# Poseidon_SystemModule.net
KiCad netlist of a schematic drawn in Altium Designer
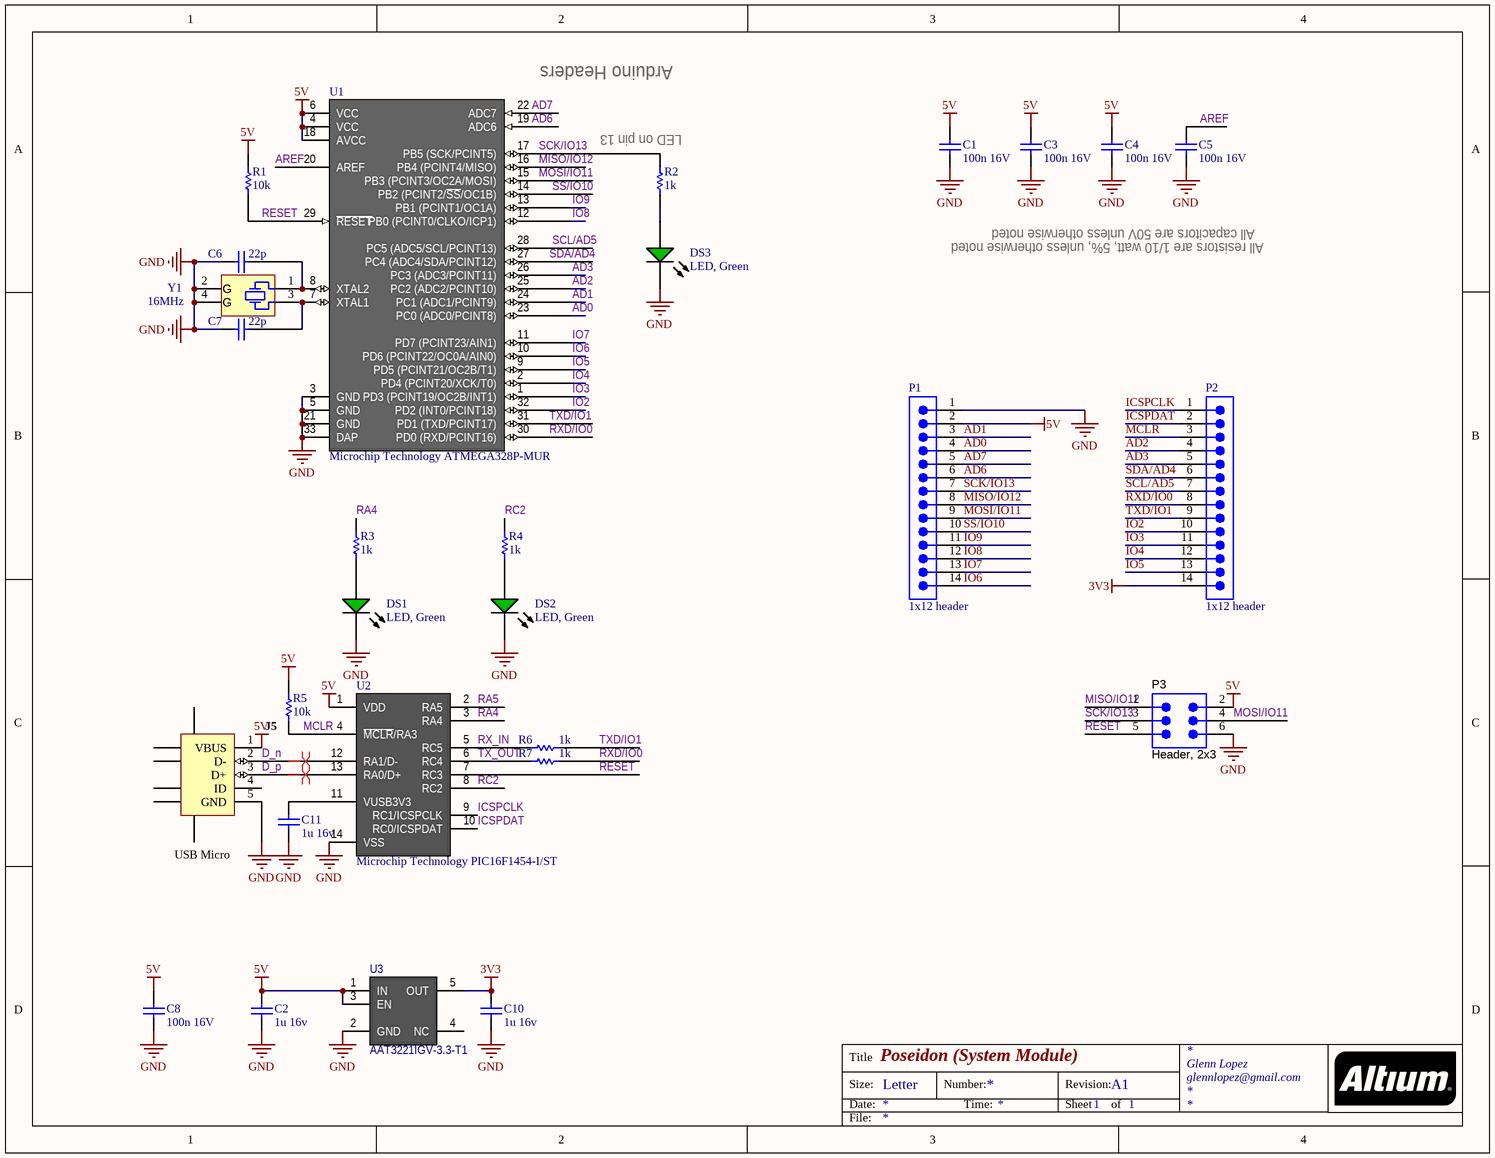
[diagram p0: Poseidon_SystemModule.SchDoc]

(export (version "E")
  (design (tool "Eeschema 10.0.6"))
  (components
    (comp (ref "C1")
      (value "100n 16V")
      (footprint "CAPC1005X55X30NL05T10")
      (description "Multilayer Ceramic Capacitors MLCC - SMD/SMT 16volts 0.1uF X7R 5%")
      (fields (field (name "MANUFACTURER PART NUMBER") "C0402C104J4RACTU") (field (name "TOLERANCE") "5 %"))
      (libsource (lib "CommunityVault") (part "CAP-2"))
    )
    (comp (ref "C2")
      (value "1u 16v")
      (footprint "CAPC1608X90X35ML15T15")
      (description "CAP CER 1UF 16V 10% X5R 0603")
      (fields (field (name "MANUFACTURER PART NUMBER") "0603YD105KAT2A"))
      (libsource (lib "CommunityVault") (part "CAP-2"))
    )
    (comp (ref "C3")
      (value "100n 16V")
      (footprint "CAPC1005X55X30NL05T10")
      (description "Multilayer Ceramic Capacitors MLCC - SMD/SMT 16volts 0.1uF X7R 5%")
      (fields (field (name "MANUFACTURER PART NUMBER") "C0402C104J4RACTU") (field (name "TOLERANCE") "5 %"))
      (libsource (lib "CommunityVault") (part "CAP-2"))
    )
    (comp (ref "C4")
      (value "100n 16V")
      (footprint "CAPC1005X55X30NL05T10")
      (description "Multilayer Ceramic Capacitors MLCC - SMD/SMT 16volts 0.1uF X7R 5%")
      (fields (field (name "MANUFACTURER PART NUMBER") "C0402C104J4RACTU") (field (name "TOLERANCE") "5 %"))
      (libsource (lib "CommunityVault") (part "CAP-2"))
    )
    (comp (ref "C5")
      (value "100n 16V")
      (footprint "CAPC1005X55X30NL05T10")
      (description "Multilayer Ceramic Capacitors MLCC - SMD/SMT 16volts 0.1uF X7R 5%")
      (fields (field (name "MANUFACTURER PART NUMBER") "C0402C104J4RACTU") (field (name "TOLERANCE") "5 %"))
      (libsource (lib "CommunityVault") (part "CAP-2"))
    )
    (comp (ref "C6")
      (value "22p")
      (footprint "CAPC1005X55X25LL05T05")
      (description "CAP CER 22PF 50V 5% NPO 0402")
      (fields (field (name "TOLERANCE") "±5%") (field (name "MANUFACTURER PART NUMBER") "CC0402JRNPO9BN220"))
      (libsource (lib "CommunityVault") (part "CAP-NP-2"))
    )
    (comp (ref "C7")
      (value "22p")
      (footprint "CAPC1005X55X25LL05T05")
      (description "CAP CER 22PF 50V 5% NPO 0402")
      (fields (field (name "TOLERANCE") "±5%") (field (name "MANUFACTURER PART NUMBER") "CC0402JRNPO9BN220"))
      (libsource (lib "CommunityVault") (part "CAP-NP-2"))
    )
    (comp (ref "C8")
      (value "100n 16V")
      (footprint "CAPC1005X55X30NL05T10")
      (description "Multilayer Ceramic Capacitors MLCC - SMD/SMT 16volts 0.1uF X7R 5%")
      (fields (field (name "MANUFACTURER PART NUMBER") "C0402C104J4RACTU") (field (name "TOLERANCE") "5 %"))
      (libsource (lib "CommunityVault") (part "CAP-2"))
    )
    (comp (ref "C10")
      (value "1u 16v")
      (footprint "CAPC1608X90X35ML15T15")
      (description "CAP CER 1UF 16V 10% X5R 0603")
      (fields (field (name "MANUFACTURER PART NUMBER") "0603YD105KAT2A"))
      (libsource (lib "CommunityVault") (part "CAP-2"))
    )
    (comp (ref "C11")
      (value "1u 16v")
      (footprint "CAPC1608X90X35ML15T15")
      (description "CAP CER 1UF 16V 10% X5R 0603")
      (fields (field (name "MANUFACTURER PART NUMBER") "0603YD105KAT2A"))
      (libsource (lib "CommunityVault") (part "CAP-2"))
    )
    (comp (ref "DS1")
      (value "LED, Green")
      (footprint "LTON_LTST-C190GKT")
      (description "LED GREEN CLEAR 0603 SMD")
      (fields (field (name "MANUFACTURER PART NUMBER") "LTST-C190GKT"))
      (libsource (lib "CommunityVault") (part "LED_GREEN_A1K2-2"))
    )
    (comp (ref "DS2")
      (value "LED, Green")
      (footprint "LTON_LTST-C190GKT")
      (description "LED GREEN CLEAR 0603 SMD")
      (fields (field (name "MANUFACTURER PART NUMBER") "LTST-C190GKT"))
      (libsource (lib "CommunityVault") (part "LED_GREEN_A1K2-2"))
    )
    (comp (ref "DS3")
      (value "LED, Green")
      (footprint "LTON_LTST-C190GKT")
      (description "LED GREEN CLEAR 0603 SMD")
      (fields (field (name "MANUFACTURER PART NUMBER") "LTST-C190GKT"))
      (libsource (lib "CommunityVault") (part "LED_GREEN_A1K2-2"))
    )
    (comp (ref "J5")
      (value "USB Micro")
      (footprint "HIRO-ZX62R-B-5P_V")
      (description "Connector; USBMicro-B,Reverse type, SMT; 5 Position; Right Angle")
      (fields (field (name "MANUFACTURER") "Hirose Electric (HRS)"))
      (libsource (lib "CommunityVault") (part "HIRO-ZX62R-B-5P-5"))
    )
    (comp (ref "P1")
      (value "1x12 header")
      (footprint "PCB-3412241-1")
      (description "Headers & Wire Housings 2.54MM BREAKAWAY Vertical 14 CKT Tin")
      (fields (field (name "MANUFACTURER PART NUMBER") "22-28-4140") (field (name "MANUFACTURER") "Molex"))
      (libsource (lib "CommunityVault") (part "CMP-3412241-A.4"))
    )
    (comp (ref "P2")
      (value "1x12 header")
      (footprint "PCB-3412241-1")
      (description "Headers & Wire Housings 2.54MM BREAKAWAY Vertical 14 CKT Tin")
      (fields (field (name "MANUFACTURER PART NUMBER") "22-28-4140") (field (name "MANUFACTURER") "Molex"))
      (libsource (lib "CommunityVault") (part "CMP-3412241-A.4"))
    )
    (comp (ref "P3")
      (value "Header, 2x3")
      (footprint "2X03")
      (fields (field (name "MANUFACTURER PART NUMBER") "826656-3"))
      (libsource (lib "CommunityVault") (part "Header_3x2"))
    )
    (comp (ref "R1")
      (value "10k")
      (footprint "RESC1005X40X25NL05T10")
      (description "YAGEO (PHYCOMP)   RC0402FR-0710KL   RESISTOR, 10K, 1%, 0.063W, 0402")
      (fields (field (name "TOLERANCE") "1 %") (field (name "MANUFACTURER PART NUMBER") "RC0402FR-0710KL"))
      (libsource (lib "CommunityVault") (part "RES-2"))
    )
    (comp (ref "R2")
      (value "1k")
      (footprint "RESC1005X40X25ML10T10")
      (description "MULTICOMP   MC 0.0625W 0402 1% 215K   RESISTOR, 0402, 1%, 215K")
      (fields (field (name "MANUFACTURER PART NUMBER") "MC00625W04021215K"))
      (libsource (lib "CommunityVault") (part "RES-2"))
    )
    (comp (ref "R3")
      (value "1k")
      (footprint "RESC1005X40X25ML10T10")
      (description "MULTICOMP   MC 0.0625W 0402 1% 215K   RESISTOR, 0402, 1%, 215K")
      (fields (field (name "MANUFACTURER PART NUMBER") "MC00625W04021215K"))
      (libsource (lib "CommunityVault") (part "RES-2"))
    )
    (comp (ref "R4")
      (value "1k")
      (footprint "RESC1005X40X25ML10T10")
      (description "MULTICOMP   MC 0.0625W 0402 1% 215K   RESISTOR, 0402, 1%, 215K")
      (fields (field (name "MANUFACTURER PART NUMBER") "MC00625W04021215K"))
      (libsource (lib "CommunityVault") (part "RES-2"))
    )
    (comp (ref "R5")
      (value "10k")
      (footprint "RESC1005X40X25NL05T10")
      (description "YAGEO (PHYCOMP)   RC0402FR-0710KL   RESISTOR, 10K, 1%, 0.063W, 0402")
      (fields (field (name "TOLERANCE") "1 %") (field (name "MANUFACTURER PART NUMBER") "RC0402FR-0710KL"))
      (libsource (lib "CommunityVault") (part "RES-2"))
    )
    (comp (ref "R6")
      (value "1k")
      (footprint "RESC1005X40X25ML10T10")
      (description "MULTICOMP   MC 0.0625W 0402 1% 215K   RESISTOR, 0402, 1%, 215K")
      (fields (field (name "MANUFACTURER PART NUMBER") "MC00625W04021215K"))
      (libsource (lib "CommunityVault") (part "RES-2"))
    )
    (comp (ref "R7")
      (value "1k")
      (footprint "RESC1005X40X25ML10T10")
      (description "MULTICOMP   MC 0.0625W 0402 1% 215K   RESISTOR, 0402, 1%, 215K")
      (fields (field (name "MANUFACTURER PART NUMBER") "MC00625W04021215K"))
      (libsource (lib "CommunityVault") (part "RES-2"))
    )
    (comp (ref "U1")
      (value "Microchip Technology ATMEGA328P-MUR")
      (footprint "PCB-1210586-1")
      (description "MCU AVR 32K FLASH 20MHZ 32QFN")
      (fields
        (field (name "MANUFACTURER") "Microchip Technology")
        (field (name "MANUFACTURER PART NUMBER") "ATMEGA328P-MUR")
      )
      (libsource (lib "CommunityVault") (part "SYM-1210586-1"))
    )
    (comp (ref "U2")
      (value "Microchip Technology PIC16F1454-I/ST")
      (footprint "PCB-4286474-1")
      (description "Microcontroller 8 Bit TSSOP-14, PIC16F1454-I/ST")
      (fields (field (name "MANUFACTURER PART NUMBER") "PIC16F1454-I/ST"))
      (libsource (lib "CommunityVault") (part "SYM-4286474-1"))
    )
    (comp (ref "U3")
      (value "AAT3221IGV-3.3-T1")
      (footprint "PCB-8081266-1")
      (description "Low Dropout Regulators - LDO 150mA NanoPower LDO Linear Regulator")
      (libsource (lib "CommunityVault") (part "SYM-8081266-1"))
    )
    (comp (ref "Y1")
      (value "16MHz")
      (footprint "ABCN-ABM3B")
      (description "CRYSTAL 16.000MHZ 18PF SMD")
      (fields (field (name "MANUFACTURER PART NUMBER") "ABM3B-16.000MHZ-B2-T"))
      (libsource (lib "CommunityVault") (part "XTAL_4P_13_G24"))
    )
  )
  (nets
    (net (code "1") (name "/AD0") (class "Default")
      (node (ref "P1") (pin "4") (pinfunction "4_4") (pintype "passive"))
      (node (ref "U1") (pin "23") (pinfunction "PC0_(ADC0/PCINT8)_23") (pintype "bidirectional"))
    )
    (net (code "2") (name "/AD1") (class "Default")
      (node (ref "P1") (pin "3") (pinfunction "3_3") (pintype "passive"))
      (node (ref "U1") (pin "24") (pinfunction "PC1_(ADC1/PCINT9)_24") (pintype "bidirectional"))
    )
    (net (code "3") (name "/AD2") (class "Default")
      (node (ref "P2") (pin "4") (pinfunction "4_4") (pintype "passive"))
      (node (ref "U1") (pin "25") (pinfunction "PC2_(ADC2/PCINT10)_25") (pintype "bidirectional"))
    )
    (net (code "4") (name "/AD3") (class "Default")
      (node (ref "P2") (pin "5") (pinfunction "5_5") (pintype "passive"))
      (node (ref "U1") (pin "26") (pinfunction "PC3_(ADC3/PCINT11)_26") (pintype "bidirectional"))
    )
    (net (code "5") (name "/AD6") (class "Default")
      (node (ref "P1") (pin "6") (pinfunction "6_6") (pintype "passive"))
      (node (ref "U1") (pin "19") (pinfunction "ADC6_19") (pintype "input"))
    )
    (net (code "6") (name "/AD7") (class "Default")
      (node (ref "P1") (pin "5") (pinfunction "5_5") (pintype "passive"))
      (node (ref "U1") (pin "22") (pinfunction "ADC7_22") (pintype "input"))
    )
    (net (code "7") (name "/AREF") (class "Default")
      (node (ref "C5") (pin "2") (pinfunction "2_2") (pintype "passive"))
      (node (ref "U1") (pin "20") (pinfunction "AREF_20") (pintype "power_in"))
    )
    (net (code "8") (name "/D_n") (class "Default")
      (node (ref "J5") (pin "2") (pinfunction "D-_2") (pintype "bidirectional"))
      (node (ref "U2") (pin "12") (pinfunction "RA1/D-_12") (pintype "passive"))
    )
    (net (code "9") (name "/D_p") (class "Default")
      (node (ref "J5") (pin "3") (pinfunction "D+_3") (pintype "bidirectional"))
      (node (ref "U2") (pin "13") (pinfunction "RA0/D+_13") (pintype "passive"))
    )
    (net (code "10") (name "/ICSPCLK") (class "Default")
      (node (ref "P2") (pin "1") (pinfunction "1_1") (pintype "passive"))
      (node (ref "U2") (pin "9") (pinfunction "RC1/ICSPCLK_9") (pintype "passive"))
    )
    (net (code "11") (name "/ICSPDAT") (class "Default")
      (node (ref "P2") (pin "2") (pinfunction "2_2") (pintype "passive"))
      (node (ref "U2") (pin "10") (pinfunction "RC0/ICSPDAT_10") (pintype "passive"))
    )
    (net (code "12") (name "/IO2") (class "Default")
      (node (ref "P2") (pin "10") (pinfunction "10_10") (pintype "passive"))
      (node (ref "U1") (pin "32") (pinfunction "PD2_(INT0/PCINT18)_32") (pintype "bidirectional"))
    )
    (net (code "13") (name "/IO3") (class "Default")
      (node (ref "P2") (pin "11") (pinfunction "11_11") (pintype "passive"))
      (node (ref "U1") (pin "1") (pinfunction "PD3_(PCINT19/OC2B/INT1)_1") (pintype "bidirectional"))
    )
    (net (code "14") (name "/IO4") (class "Default")
      (node (ref "P2") (pin "12") (pinfunction "12_12") (pintype "passive"))
      (node (ref "U1") (pin "2") (pinfunction "PD4_(PCINT20/XCK/T0)_2") (pintype "bidirectional"))
    )
    (net (code "15") (name "/IO5") (class "Default")
      (node (ref "P2") (pin "13") (pinfunction "13_13") (pintype "passive"))
      (node (ref "U1") (pin "9") (pinfunction "PD5_(PCINT21/OC2B/T1)_9") (pintype "bidirectional"))
    )
    (net (code "16") (name "/IO6") (class "Default")
      (node (ref "P1") (pin "14") (pinfunction "14_14") (pintype "passive"))
      (node (ref "U1") (pin "10") (pinfunction "PD6_(PCINT22/OC0A/AIN0)_10") (pintype "bidirectional"))
    )
    (net (code "17") (name "/IO7") (class "Default")
      (node (ref "P1") (pin "13") (pinfunction "13_13") (pintype "passive"))
      (node (ref "U1") (pin "11") (pinfunction "PD7_(PCINT23/AIN1)_11") (pintype "bidirectional"))
    )
    (net (code "18") (name "/IO8") (class "Default")
      (node (ref "P1") (pin "12") (pinfunction "12_12") (pintype "passive"))
      (node (ref "U1") (pin "12") (pinfunction "PB0_(PCINT0/CLKO/ICP1)_12") (pintype "bidirectional"))
    )
    (net (code "19") (name "/IO9") (class "Default")
      (node (ref "P1") (pin "11") (pinfunction "11_11") (pintype "passive"))
      (node (ref "U1") (pin "13") (pinfunction "PB1_(PCINT1/OC1A)_13") (pintype "bidirectional"))
    )
    (net (code "20") (name "/MCLR") (class "Default")
      (node (ref "P2") (pin "3") (pinfunction "3_3") (pintype "passive"))
      (node (ref "R5") (pin "1") (pinfunction "1_1") (pintype "passive"))
      (node (ref "U2") (pin "4") (pinfunction "~{MCLR}/RA3_4") (pintype "passive"))
    )
    (net (code "21") (name "/MISO{slash}IO12") (class "Default")
      (node (ref "P1") (pin "8") (pinfunction "8_8") (pintype "passive"))
      (node (ref "P3") (pin "1") (pinfunction "1_1") (pintype "passive"))
      (node (ref "U1") (pin "16") (pinfunction "PB4_(PCINT4/MISO)_16") (pintype "bidirectional"))
    )
    (net (code "22") (name "/MOSI{slash}IO11") (class "Default")
      (node (ref "P1") (pin "9") (pinfunction "9_9") (pintype "passive"))
      (node (ref "P3") (pin "4") (pinfunction "4_4") (pintype "passive"))
      (node (ref "U1") (pin "15") (pinfunction "PB3_(PCINT3/OC2A/MOSI)_15") (pintype "bidirectional"))
    )
    (net (code "23") (name "/RA4") (class "Default")
      (node (ref "R3") (pin "2") (pinfunction "2_2") (pintype "passive"))
      (node (ref "U2") (pin "3") (pinfunction "RA4_3") (pintype "passive"))
    )
    (net (code "24") (name "/RA5") (class "Default")
      (node (ref "U2") (pin "2") (pinfunction "RA5_2") (pintype "passive"))
    )
    (net (code "25") (name "/RC2") (class "Default")
      (node (ref "R4") (pin "2") (pinfunction "2_2") (pintype "passive"))
      (node (ref "U2") (pin "8") (pinfunction "RC2_8") (pintype "passive"))
    )
    (net (code "26") (name "/RESET") (class "Default")
      (node (ref "P3") (pin "5") (pinfunction "5_5") (pintype "passive"))
      (node (ref "R1") (pin "1") (pinfunction "1_1") (pintype "passive"))
      (node (ref "U1") (pin "29") (pinfunction "~{RESET}_29") (pintype "input"))
      (node (ref "U2") (pin "7") (pinfunction "RC3_7") (pintype "passive"))
    )
    (net (code "27") (name "/RXD{slash}IO0") (class "Default")
      (node (ref "P2") (pin "8") (pinfunction "8_8") (pintype "passive"))
      (node (ref "R7") (pin "1") (pinfunction "1_1") (pintype "passive"))
      (node (ref "U1") (pin "30") (pinfunction "PD0_(RXD/PCINT16)_30") (pintype "bidirectional"))
    )
    (net (code "28") (name "/RX_IN") (class "Default")
      (node (ref "R6") (pin "2") (pinfunction "2_2") (pintype "passive"))
      (node (ref "U2") (pin "5") (pinfunction "RC5_5") (pintype "passive"))
    )
    (net (code "29") (name "/SCK{slash}IO13") (class "Default")
      (node (ref "P1") (pin "7") (pinfunction "7_7") (pintype "passive"))
      (node (ref "P3") (pin "3") (pinfunction "3_3") (pintype "passive"))
      (node (ref "R2") (pin "2") (pinfunction "2_2") (pintype "passive"))
      (node (ref "U1") (pin "17") (pinfunction "PB5_(SCK/PCINT5)_17") (pintype "bidirectional"))
    )
    (net (code "30") (name "/SCL{slash}AD5") (class "Default")
      (node (ref "P2") (pin "7") (pinfunction "7_7") (pintype "passive"))
      (node (ref "U1") (pin "28") (pinfunction "PC5_(ADC5/SCL/PCINT13)_28") (pintype "bidirectional"))
    )
    (net (code "31") (name "/SDA{slash}AD4") (class "Default")
      (node (ref "P2") (pin "6") (pinfunction "6_6") (pintype "passive"))
      (node (ref "U1") (pin "27") (pinfunction "PC4_(ADC4/SDA/PCINT12)_27") (pintype "bidirectional"))
    )
    (net (code "32") (name "/SS{slash}IO10") (class "Default")
      (node (ref "P1") (pin "10") (pinfunction "10_10") (pintype "passive"))
      (node (ref "U1") (pin "14") (pinfunction "PB2_(PCINT2/~{SS}/OC1B)_14") (pintype "bidirectional"))
    )
    (net (code "33") (name "/TXD{slash}IO1") (class "Default")
      (node (ref "P2") (pin "9") (pinfunction "9_9") (pintype "passive"))
      (node (ref "R6") (pin "1") (pinfunction "1_1") (pintype "passive"))
      (node (ref "U1") (pin "31") (pinfunction "PD1_(TXD/PCINT17)_31") (pintype "bidirectional"))
    )
    (net (code "34") (name "/TX_OUT") (class "Default")
      (node (ref "R7") (pin "2") (pinfunction "2_2") (pintype "passive"))
      (node (ref "U2") (pin "6") (pinfunction "RC4_6") (pintype "passive"))
    )
    (net (code "35") (name "3V3") (class "Default")
      (node (ref "C10") (pin "2") (pinfunction "2_2") (pintype "passive"))
      (node (ref "P2") (pin "14") (pinfunction "14_14") (pintype "passive"))
      (node (ref "U3") (pin "5") (pinfunction "OUT_5") (pintype "passive"))
    )
    (net (code "36") (name "5V") (class "Default")
      (node (ref "C1") (pin "2") (pinfunction "2_2") (pintype "passive"))
      (node (ref "C2") (pin "2") (pinfunction "2_2") (pintype "passive"))
      (node (ref "C3") (pin "2") (pinfunction "2_2") (pintype "passive"))
      (node (ref "C4") (pin "2") (pinfunction "2_2") (pintype "passive"))
      (node (ref "C8") (pin "2") (pinfunction "2_2") (pintype "passive"))
      (node (ref "J5") (pin "1") (pinfunction "VBUS_1") (pintype "power_in"))
      (node (ref "P1") (pin "2") (pinfunction "2_2") (pintype "passive"))
      (node (ref "P3") (pin "2") (pinfunction "2_2") (pintype "passive"))
      (node (ref "R1") (pin "2") (pinfunction "2_2") (pintype "passive"))
      (node (ref "R5") (pin "2") (pinfunction "2_2") (pintype "passive"))
      (node (ref "U1") (pin "18") (pinfunction "AVCC_18") (pintype "power_in"))
      (node (ref "U1") (pin "4") (pinfunction "VCC_4") (pintype "power_in"))
      (node (ref "U1") (pin "6") (pinfunction "VCC_6") (pintype "power_in"))
      (node (ref "U2") (pin "1") (pinfunction "VDD_1") (pintype "passive"))
      (node (ref "U3") (pin "1") (pinfunction "IN_1") (pintype "passive"))
      (node (ref "U3") (pin "3") (pinfunction "EN_3") (pintype "passive"))
    )
    (net (code "37") (name "GND") (class "Default")
      (node (ref "C1") (pin "1") (pinfunction "1_1") (pintype "passive"))
      (node (ref "C10") (pin "1") (pinfunction "1_1") (pintype "passive"))
      (node (ref "C11") (pin "1") (pinfunction "1_1") (pintype "passive"))
      (node (ref "C2") (pin "1") (pinfunction "1_1") (pintype "passive"))
      (node (ref "C3") (pin "1") (pinfunction "1_1") (pintype "passive"))
      (node (ref "C4") (pin "1") (pinfunction "1_1") (pintype "passive"))
      (node (ref "C5") (pin "1") (pinfunction "1_1") (pintype "passive"))
      (node (ref "C6") (pin "1") (pinfunction "1_1") (pintype "passive"))
      (node (ref "C7") (pin "1") (pinfunction "1_1") (pintype "passive"))
      (node (ref "C8") (pin "1") (pinfunction "1_1") (pintype "passive"))
      (node (ref "DS1") (pin "2") (pinfunction "K_2") (pintype "passive"))
      (node (ref "DS2") (pin "2") (pinfunction "K_2") (pintype "passive"))
      (node (ref "DS3") (pin "2") (pinfunction "K_2") (pintype "passive"))
      (node (ref "J5") (pin "5") (pinfunction "GND_5") (pintype "power_in"))
      (node (ref "P1") (pin "1") (pinfunction "1_1") (pintype "passive"))
      (node (ref "P3") (pin "6") (pinfunction "6_6") (pintype "passive"))
      (node (ref "U1") (pin "21") (pinfunction "GND_21") (pintype "power_in"))
      (node (ref "U1") (pin "3") (pinfunction "GND_3") (pintype "power_in"))
      (node (ref "U1") (pin "33") (pinfunction "DAP_33") (pintype "passive"))
      (node (ref "U1") (pin "5") (pinfunction "GND_5") (pintype "power_in"))
      (node (ref "U2") (pin "14") (pinfunction "VSS_14") (pintype "passive"))
      (node (ref "U3") (pin "2") (pinfunction "GND_2") (pintype "passive"))
      (node (ref "Y1") (pin "2") (pinfunction "GND_2") (pintype "power_in"))
      (node (ref "Y1") (pin "4") (pinfunction "GND_4") (pintype "power_in"))
    )
    (net (code "38") (name "Net-(DS1-A)") (class "Default")
      (node (ref "DS1") (pin "1") (pinfunction "A_1") (pintype "passive"))
      (node (ref "R3") (pin "1") (pinfunction "1_1") (pintype "passive"))
    )
    (net (code "39") (name "Net-(DS2-A)") (class "Default")
      (node (ref "DS2") (pin "1") (pinfunction "A_1") (pintype "passive"))
      (node (ref "R4") (pin "1") (pinfunction "1_1") (pintype "passive"))
    )
    (net (code "40") (name "Net-(DS3-A)") (class "Default")
      (node (ref "DS3") (pin "1") (pinfunction "A_1") (pintype "passive"))
      (node (ref "R2") (pin "1") (pinfunction "1_1") (pintype "passive"))
    )
    (net (code "41") (name "Net-(U1-XTAL1)") (class "Default")
      (node (ref "C7") (pin "2") (pinfunction "2_2") (pintype "passive"))
      (node (ref "U1") (pin "7") (pinfunction "XTAL1_7") (pintype "bidirectional"))
      (node (ref "Y1") (pin "3") (pinfunction "3_3") (pintype "passive"))
    )
    (net (code "42") (name "Net-(U1-XTAL2)") (class "Default")
      (node (ref "C6") (pin "2") (pinfunction "2_2") (pintype "passive"))
      (node (ref "U1") (pin "8") (pinfunction "XTAL2_8") (pintype "bidirectional"))
      (node (ref "Y1") (pin "1") (pinfunction "1_1") (pintype "passive"))
    )
    (net (code "43") (name "Net-(U2-VUSB3V3)") (class "Default")
      (node (ref "C11") (pin "2") (pinfunction "2_2") (pintype "passive"))
      (node (ref "U2") (pin "11") (pinfunction "VUSB3V3_11") (pintype "passive"))
    )
    (net (code "44") (name "unconnected-(J5-ID-Pad4)") (class "Default")
      (node (ref "J5") (pin "4") (pinfunction "ID_4") (pintype "passive"))
    )
    (net (code "45") (name "unconnected-(J5-SHLD-Pad6)") (class "Default")
      (node (ref "J5") (pin "6") (pinfunction "SHLD_6") (pintype "passive"))
    )
    (net (code "46") (name "unconnected-(J5-SHLD-Pad7)") (class "Default")
      (node (ref "J5") (pin "7") (pinfunction "SHLD_7") (pintype "passive"))
    )
    (net (code "47") (name "unconnected-(J5-SHLD-Pad8)") (class "Default")
      (node (ref "J5") (pin "8") (pinfunction "SHLD_8") (pintype "passive"))
    )
    (net (code "48") (name "unconnected-(J5-SHLD-Pad9)") (class "Default")
      (node (ref "J5") (pin "9") (pinfunction "SHLD_9") (pintype "passive"))
    )
    (net (code "49") (name "unconnected-(J5-SHLD-Pad10)") (class "Default")
      (node (ref "J5") (pin "10") (pinfunction "SHLD_10") (pintype "passive"))
    )
    (net (code "50") (name "unconnected-(J5-SHLD-Pad11)") (class "Default")
      (node (ref "J5") (pin "11") (pinfunction "SHLD_11") (pintype "passive"))
    )
    (net (code "51") (name "unconnected-(U3-NC-Pad4)") (class "Default")
      (node (ref "U3") (pin "4") (pinfunction "NC_4") (pintype "passive"))
    )
  )
)
